# ct_userio.net
KiCad netlist of a schematic drawn in Altium Designer
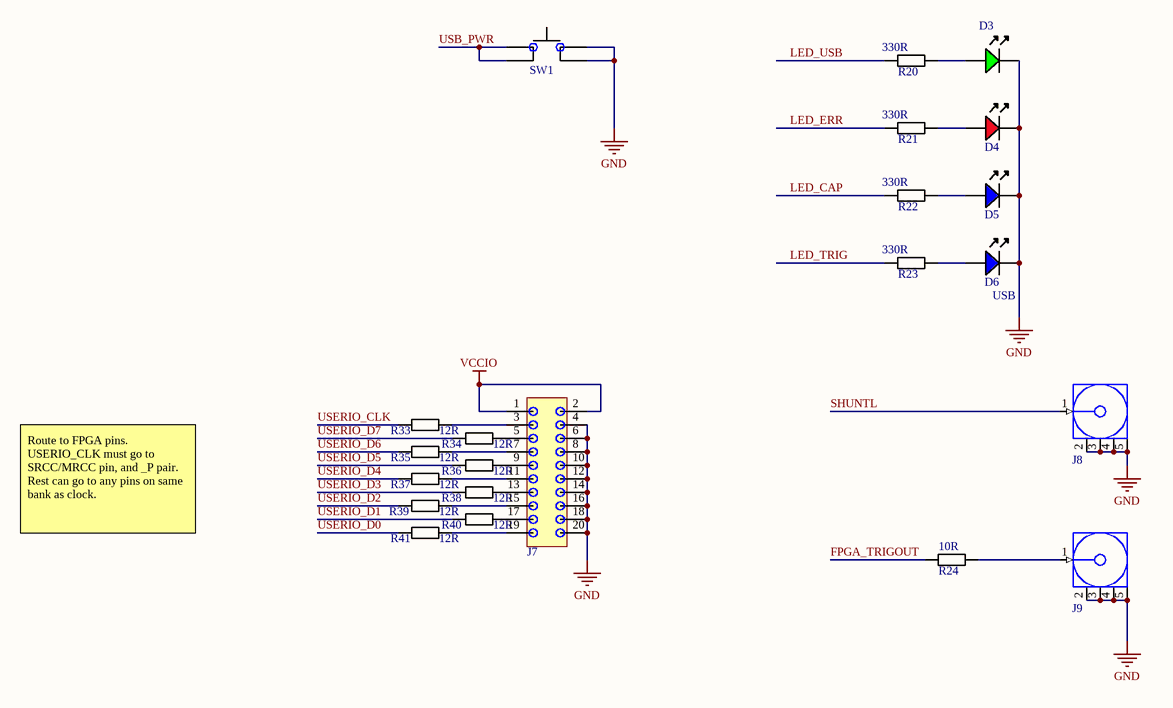
[diagram p0: ct_userio.SchDoc]

(export (version "E")
  (design (tool "Eeschema 10.0.6"))
  (components
    (comp (ref "D3")
      (value "~")
      (footprint "LED-0603-GREEN")
      (description "Chip LED, Green")
      (fields (field (name "PART NUMBER") "LEDCHIP_0603_GREEN"))
      (libsource (lib "NewAE_AltiumLib") (part "LED_GREEN"))
    )
    (comp (ref "D4")
      (value "LED, 0603, Red")
      (footprint "LED-0603-RED")
      (description "Chip LED, Red")
      (fields (field (name "PART NUMBER") "LEDCHIP_0603_RED"))
      (libsource (lib "NewAE_AltiumLib") (part "LED_RED"))
    )
    (comp (ref "D5")
      (value "LED, 0603, Blue")
      (footprint "LED-0603-BLUE")
      (description "Chip LED, Blue")
      (fields (field (name "PART NUMBER") "LEDCHIP_0603_BLUE"))
      (libsource (lib "NewAE_AltiumLib") (part "LED_BLUE"))
    )
    (comp (ref "D6")
      (value "USB")
      (footprint "LED-0603-BLUE")
      (description "Chip LED, Blue")
      (fields (field (name "PART NUMBER") "LEDCHIP_0603_BLUE"))
      (libsource (lib "NewAE_AltiumLib") (part "LED_BLUE"))
    )
    (comp (ref "J7")
      (value "EW-10-09-G-D-300")
      (footprint "EW-10-09-G-D-300")
      (description "20-Pin Header, High-Top")
      (fields (field (name "PART NUMBER") "SBH11-PBPC-D10-ST-BK"))
      (libsource (lib "NewAE_AltiumLib") (part "CON20_2ROW"))
    )
    (comp (ref "J8")
      (value "MCX 733660061")
      (footprint "CONN_MCX_733660061")
      (description "MCX Straight")
      (fields (field (name "PART NUMBER") "733660061"))
      (libsource (lib "NewAE_AltiumLib") (part "CON-SMA-PCBEDGE-003.062"))
    )
    (comp (ref "J9")
      (value "MCX 733660061")
      (footprint "CONN_MCX_733660061")
      (description "MCX Straight")
      (fields (field (name "PART NUMBER") "733660061"))
      (libsource (lib "NewAE_AltiumLib") (part "CON-SMA-PCBEDGE-003.062"))
    )
    (comp (ref "R20")
      (value "330R")
      (footprint "RESC1608X55N")
      (description "330R res, 0603, 1%, 1/10W")
      (fields (field (name "PART NUMBER") "RCHIP-330R-0603") (field (name "TOLERANCE") "1%"))
      (libsource (lib "NewAE_AltiumLib") (part "RES-EU"))
    )
    (comp (ref "R21")
      (value "330R")
      (footprint "RESC1608X55N")
      (description "330R res, 0603, 1%, 1/10W")
      (fields (field (name "PART NUMBER") "RCHIP-330R-0603") (field (name "TOLERANCE") "1%"))
      (libsource (lib "NewAE_AltiumLib") (part "RES-EU"))
    )
    (comp (ref "R22")
      (value "330R")
      (footprint "RESC1608X55N")
      (description "330R res, 0603, 1%, 1/10W")
      (fields (field (name "PART NUMBER") "RCHIP-330R-0603") (field (name "TOLERANCE") "1%"))
      (libsource (lib "NewAE_AltiumLib") (part "RES-EU"))
    )
    (comp (ref "R23")
      (value "330R")
      (footprint "RESC1608X55N")
      (description "330R res, 0603, 1%, 1/10W")
      (fields (field (name "PART NUMBER") "RCHIP-330R-0603") (field (name "TOLERANCE") "1%"))
      (libsource (lib "NewAE_AltiumLib") (part "RES-EU"))
    )
    (comp (ref "R24")
      (value "10R")
      (footprint "RESC1608X55N")
      (description "10R res, 0603, 1%, 1/10W")
      (fields (field (name "PART NUMBER") "RCHIP-10R-0603") (field (name "TOLERANCE") "1%"))
      (libsource (lib "NewAE_AltiumLib") (part "RES-EU"))
    )
    (comp (ref "R33")
      (value "12R")
      (footprint "RESC1005X40N")
      (description "12R res, 0402, 1%, 1/16W")
      (fields (field (name "PART NUMBER") "RCHIP-12R-0402") (field (name "TOLERANCE") "1%"))
      (libsource (lib "NewAE_AltiumLib") (part "RES-EU"))
    )
    (comp (ref "R34")
      (value "12R")
      (footprint "RESC1005X40N")
      (description "12R res, 0402, 1%, 1/16W")
      (fields (field (name "PART NUMBER") "RCHIP-12R-0402") (field (name "TOLERANCE") "1%"))
      (libsource (lib "NewAE_AltiumLib") (part "RES-EU"))
    )
    (comp (ref "R35")
      (value "12R")
      (footprint "RESC1005X40N")
      (description "12R res, 0402, 1%, 1/16W")
      (fields (field (name "PART NUMBER") "RCHIP-12R-0402") (field (name "TOLERANCE") "1%"))
      (libsource (lib "NewAE_AltiumLib") (part "RES-EU"))
    )
    (comp (ref "R36")
      (value "12R")
      (footprint "RESC1005X40N")
      (description "12R res, 0402, 1%, 1/16W")
      (fields (field (name "PART NUMBER") "RCHIP-12R-0402") (field (name "TOLERANCE") "1%"))
      (libsource (lib "NewAE_AltiumLib") (part "RES-EU"))
    )
    (comp (ref "R37")
      (value "12R")
      (footprint "RESC1005X40N")
      (description "12R res, 0402, 1%, 1/16W")
      (fields (field (name "PART NUMBER") "RCHIP-12R-0402") (field (name "TOLERANCE") "1%"))
      (libsource (lib "NewAE_AltiumLib") (part "RES-EU"))
    )
    (comp (ref "R38")
      (value "12R")
      (footprint "RESC1005X40N")
      (description "12R res, 0402, 1%, 1/16W")
      (fields (field (name "PART NUMBER") "RCHIP-12R-0402") (field (name "TOLERANCE") "1%"))
      (libsource (lib "NewAE_AltiumLib") (part "RES-EU"))
    )
    (comp (ref "R39")
      (value "12R")
      (footprint "RESC1005X40N")
      (description "12R res, 0402, 1%, 1/16W")
      (fields (field (name "PART NUMBER") "RCHIP-12R-0402") (field (name "TOLERANCE") "1%"))
      (libsource (lib "NewAE_AltiumLib") (part "RES-EU"))
    )
    (comp (ref "R40")
      (value "12R")
      (footprint "RESC1005X40N")
      (description "12R res, 0402, 1%, 1/16W")
      (fields (field (name "PART NUMBER") "RCHIP-12R-0402") (field (name "TOLERANCE") "1%"))
      (libsource (lib "NewAE_AltiumLib") (part "RES-EU"))
    )
    (comp (ref "R41")
      (value "12R")
      (footprint "RESC1005X40N")
      (description "12R res, 0402, 1%, 1/16W")
      (fields (field (name "PART NUMBER") "RCHIP-12R-0402") (field (name "TOLERANCE") "1%"))
      (libsource (lib "NewAE_AltiumLib") (part "RES-EU"))
    )
    (comp (ref "SW1")
      (value "KSC741J LFS")
      (footprint "CK_KSC7J")
      (description "SWITCH TACTILE SPST-NO 0.01A 32V")
      (fields (field (name "PART NUMBER") "TACTSW-KSC741J"))
      (libsource (lib "NewAE_AltiumLib") (part "SW_PB_NO_4PIN_TACT"))
    )
  )
  (nets
    (net (code "1") (name "/FPGA_TRIGOUT") (class "Default")
      (node (ref "R24") (pin "1") (pinfunction "1_1") (pintype "passive"))
    )
    (net (code "2") (name "/LED_CAP") (class "Default")
      (node (ref "R22") (pin "1") (pinfunction "1_1") (pintype "passive"))
    )
    (net (code "3") (name "/LED_ERR") (class "Default")
      (node (ref "R21") (pin "1") (pinfunction "1_1") (pintype "passive"))
    )
    (net (code "4") (name "/LED_TRIG") (class "Default")
      (node (ref "R23") (pin "1") (pinfunction "1_1") (pintype "passive"))
    )
    (net (code "5") (name "/LED_USB") (class "Default")
      (node (ref "R20") (pin "1") (pinfunction "1_1") (pintype "passive"))
    )
    (net (code "6") (name "/SHUNTL") (class "Default")
      (node (ref "J8") (pin "1") (pinfunction "Signal_1") (pintype "input"))
    )
    (net (code "7") (name "/USB_PWR") (class "Default")
      (node (ref "SW1") (pin "1") (pinfunction "IN_1") (pintype "passive"))
      (node (ref "SW1") (pin "4") (pinfunction "IN_4") (pintype "passive"))
    )
    (net (code "8") (name "/USERIO_CLK") (class "Default")
      (node (ref "R33") (pin "1") (pinfunction "1_1") (pintype "passive"))
    )
    (net (code "9") (name "/USERIO_D0") (class "Default")
      (node (ref "R41") (pin "1") (pinfunction "1_1") (pintype "passive"))
    )
    (net (code "10") (name "/USERIO_D1") (class "Default")
      (node (ref "R40") (pin "1") (pinfunction "1_1") (pintype "passive"))
    )
    (net (code "11") (name "/USERIO_D2") (class "Default")
      (node (ref "R39") (pin "1") (pinfunction "1_1") (pintype "passive"))
    )
    (net (code "12") (name "/USERIO_D3") (class "Default")
      (node (ref "R38") (pin "1") (pinfunction "1_1") (pintype "passive"))
    )
    (net (code "13") (name "/USERIO_D4") (class "Default")
      (node (ref "R37") (pin "1") (pinfunction "1_1") (pintype "passive"))
    )
    (net (code "14") (name "/USERIO_D5") (class "Default")
      (node (ref "R36") (pin "1") (pinfunction "1_1") (pintype "passive"))
    )
    (net (code "15") (name "/USERIO_D6") (class "Default")
      (node (ref "R35") (pin "1") (pinfunction "1_1") (pintype "passive"))
    )
    (net (code "16") (name "/USERIO_D7") (class "Default")
      (node (ref "R34") (pin "1") (pinfunction "1_1") (pintype "passive"))
    )
    (net (code "17") (name "GND") (class "Default")
      (node (ref "D3") (pin "K") (pinfunction "K_K") (pintype "passive"))
      (node (ref "D4") (pin "K") (pinfunction "K_K") (pintype "passive"))
      (node (ref "D5") (pin "K") (pinfunction "K_K") (pintype "passive"))
      (node (ref "D6") (pin "K") (pinfunction "K_K") (pintype "passive"))
      (node (ref "J7") (pin "10") (pinfunction "10_10") (pintype "passive"))
      (node (ref "J7") (pin "12") (pinfunction "10_12") (pintype "passive"))
      (node (ref "J7") (pin "14") (pinfunction "10_14") (pintype "passive"))
      (node (ref "J7") (pin "16") (pinfunction "10_16") (pintype "passive"))
      (node (ref "J7") (pin "18") (pinfunction "10_18") (pintype "passive"))
      (node (ref "J7") (pin "20") (pinfunction "10_20") (pintype "passive"))
      (node (ref "J7") (pin "4") (pinfunction "4_4") (pintype "passive"))
      (node (ref "J7") (pin "6") (pinfunction "6_6") (pintype "passive"))
      (node (ref "J7") (pin "8") (pinfunction "8_8") (pintype "passive"))
      (node (ref "J8") (pin "2") (pinfunction "GND_2") (pintype "power_in"))
      (node (ref "J8") (pin "3") (pinfunction "GND_3") (pintype "power_in"))
      (node (ref "J8") (pin "4") (pinfunction "GND_4") (pintype "power_in"))
      (node (ref "J8") (pin "5") (pinfunction "GND_5") (pintype "power_in"))
      (node (ref "J9") (pin "2") (pinfunction "GND_2") (pintype "power_in"))
      (node (ref "J9") (pin "3") (pinfunction "GND_3") (pintype "power_in"))
      (node (ref "J9") (pin "4") (pinfunction "GND_4") (pintype "power_in"))
      (node (ref "J9") (pin "5") (pinfunction "GND_5") (pintype "power_in"))
      (node (ref "SW1") (pin "2") (pinfunction "IN_2") (pintype "passive"))
      (node (ref "SW1") (pin "3") (pinfunction "IN_3") (pintype "passive"))
    )
    (net (code "18") (name "Net-(D3-PadA)") (class "Default")
      (node (ref "D3") (pin "A") (pinfunction "A_A") (pintype "passive"))
      (node (ref "R20") (pin "2") (pinfunction "2_2") (pintype "passive"))
    )
    (net (code "19") (name "Net-(D4-PadA)") (class "Default")
      (node (ref "D4") (pin "A") (pinfunction "A_A") (pintype "passive"))
      (node (ref "R21") (pin "2") (pinfunction "2_2") (pintype "passive"))
    )
    (net (code "20") (name "Net-(D5-PadA)") (class "Default")
      (node (ref "D5") (pin "A") (pinfunction "A_A") (pintype "passive"))
      (node (ref "R22") (pin "2") (pinfunction "2_2") (pintype "passive"))
    )
    (net (code "21") (name "Net-(D6-PadA)") (class "Default")
      (node (ref "D6") (pin "A") (pinfunction "A_A") (pintype "passive"))
      (node (ref "R23") (pin "2") (pinfunction "2_2") (pintype "passive"))
    )
    (net (code "22") (name "Net-(J7-9-Pad11)") (class "Default")
      (node (ref "J7") (pin "11") (pinfunction "9_11") (pintype "passive"))
      (node (ref "R37") (pin "2") (pinfunction "2_2") (pintype "passive"))
    )
    (net (code "23") (name "Net-(J7-9-Pad13)") (class "Default")
      (node (ref "J7") (pin "13") (pinfunction "9_13") (pintype "passive"))
      (node (ref "R38") (pin "2") (pinfunction "2_2") (pintype "passive"))
    )
    (net (code "24") (name "Net-(J7-9-Pad15)") (class "Default")
      (node (ref "J7") (pin "15") (pinfunction "9_15") (pintype "passive"))
      (node (ref "R39") (pin "2") (pinfunction "2_2") (pintype "passive"))
    )
    (net (code "25") (name "Net-(J7-9-Pad17)") (class "Default")
      (node (ref "J7") (pin "17") (pinfunction "9_17") (pintype "passive"))
      (node (ref "R40") (pin "2") (pinfunction "2_2") (pintype "passive"))
    )
    (net (code "26") (name "Net-(J7-9-Pad19)") (class "Default")
      (node (ref "J7") (pin "19") (pinfunction "9_19") (pintype "passive"))
      (node (ref "R41") (pin "2") (pinfunction "2_2") (pintype "passive"))
    )
    (net (code "27") (name "Net-(J7-Pad3)") (class "Default")
      (node (ref "J7") (pin "3") (pinfunction "3_3") (pintype "passive"))
      (node (ref "R33") (pin "2") (pinfunction "2_2") (pintype "passive"))
    )
    (net (code "28") (name "Net-(J7-Pad5)") (class "Default")
      (node (ref "J7") (pin "5") (pinfunction "5_5") (pintype "passive"))
      (node (ref "R34") (pin "2") (pinfunction "2_2") (pintype "passive"))
    )
    (net (code "29") (name "Net-(J7-Pad7)") (class "Default")
      (node (ref "J7") (pin "7") (pinfunction "7_7") (pintype "passive"))
      (node (ref "R35") (pin "2") (pinfunction "2_2") (pintype "passive"))
    )
    (net (code "30") (name "Net-(J7-Pad9)") (class "Default")
      (node (ref "J7") (pin "9") (pinfunction "9_9") (pintype "passive"))
      (node (ref "R36") (pin "2") (pinfunction "2_2") (pintype "passive"))
    )
    (net (code "31") (name "Net-(J9-Signal)") (class "Default")
      (node (ref "J9") (pin "1") (pinfunction "Signal_1") (pintype "input"))
      (node (ref "R24") (pin "2") (pinfunction "2_2") (pintype "passive"))
    )
    (net (code "32") (name "VCCIO") (class "Default")
      (node (ref "J7") (pin "1") (pinfunction "1_1") (pintype "passive"))
      (node (ref "J7") (pin "2") (pinfunction "2_2") (pintype "passive"))
    )
  )
)
